# POWER.net
KiCad netlist of a schematic drawn in Altium Designer
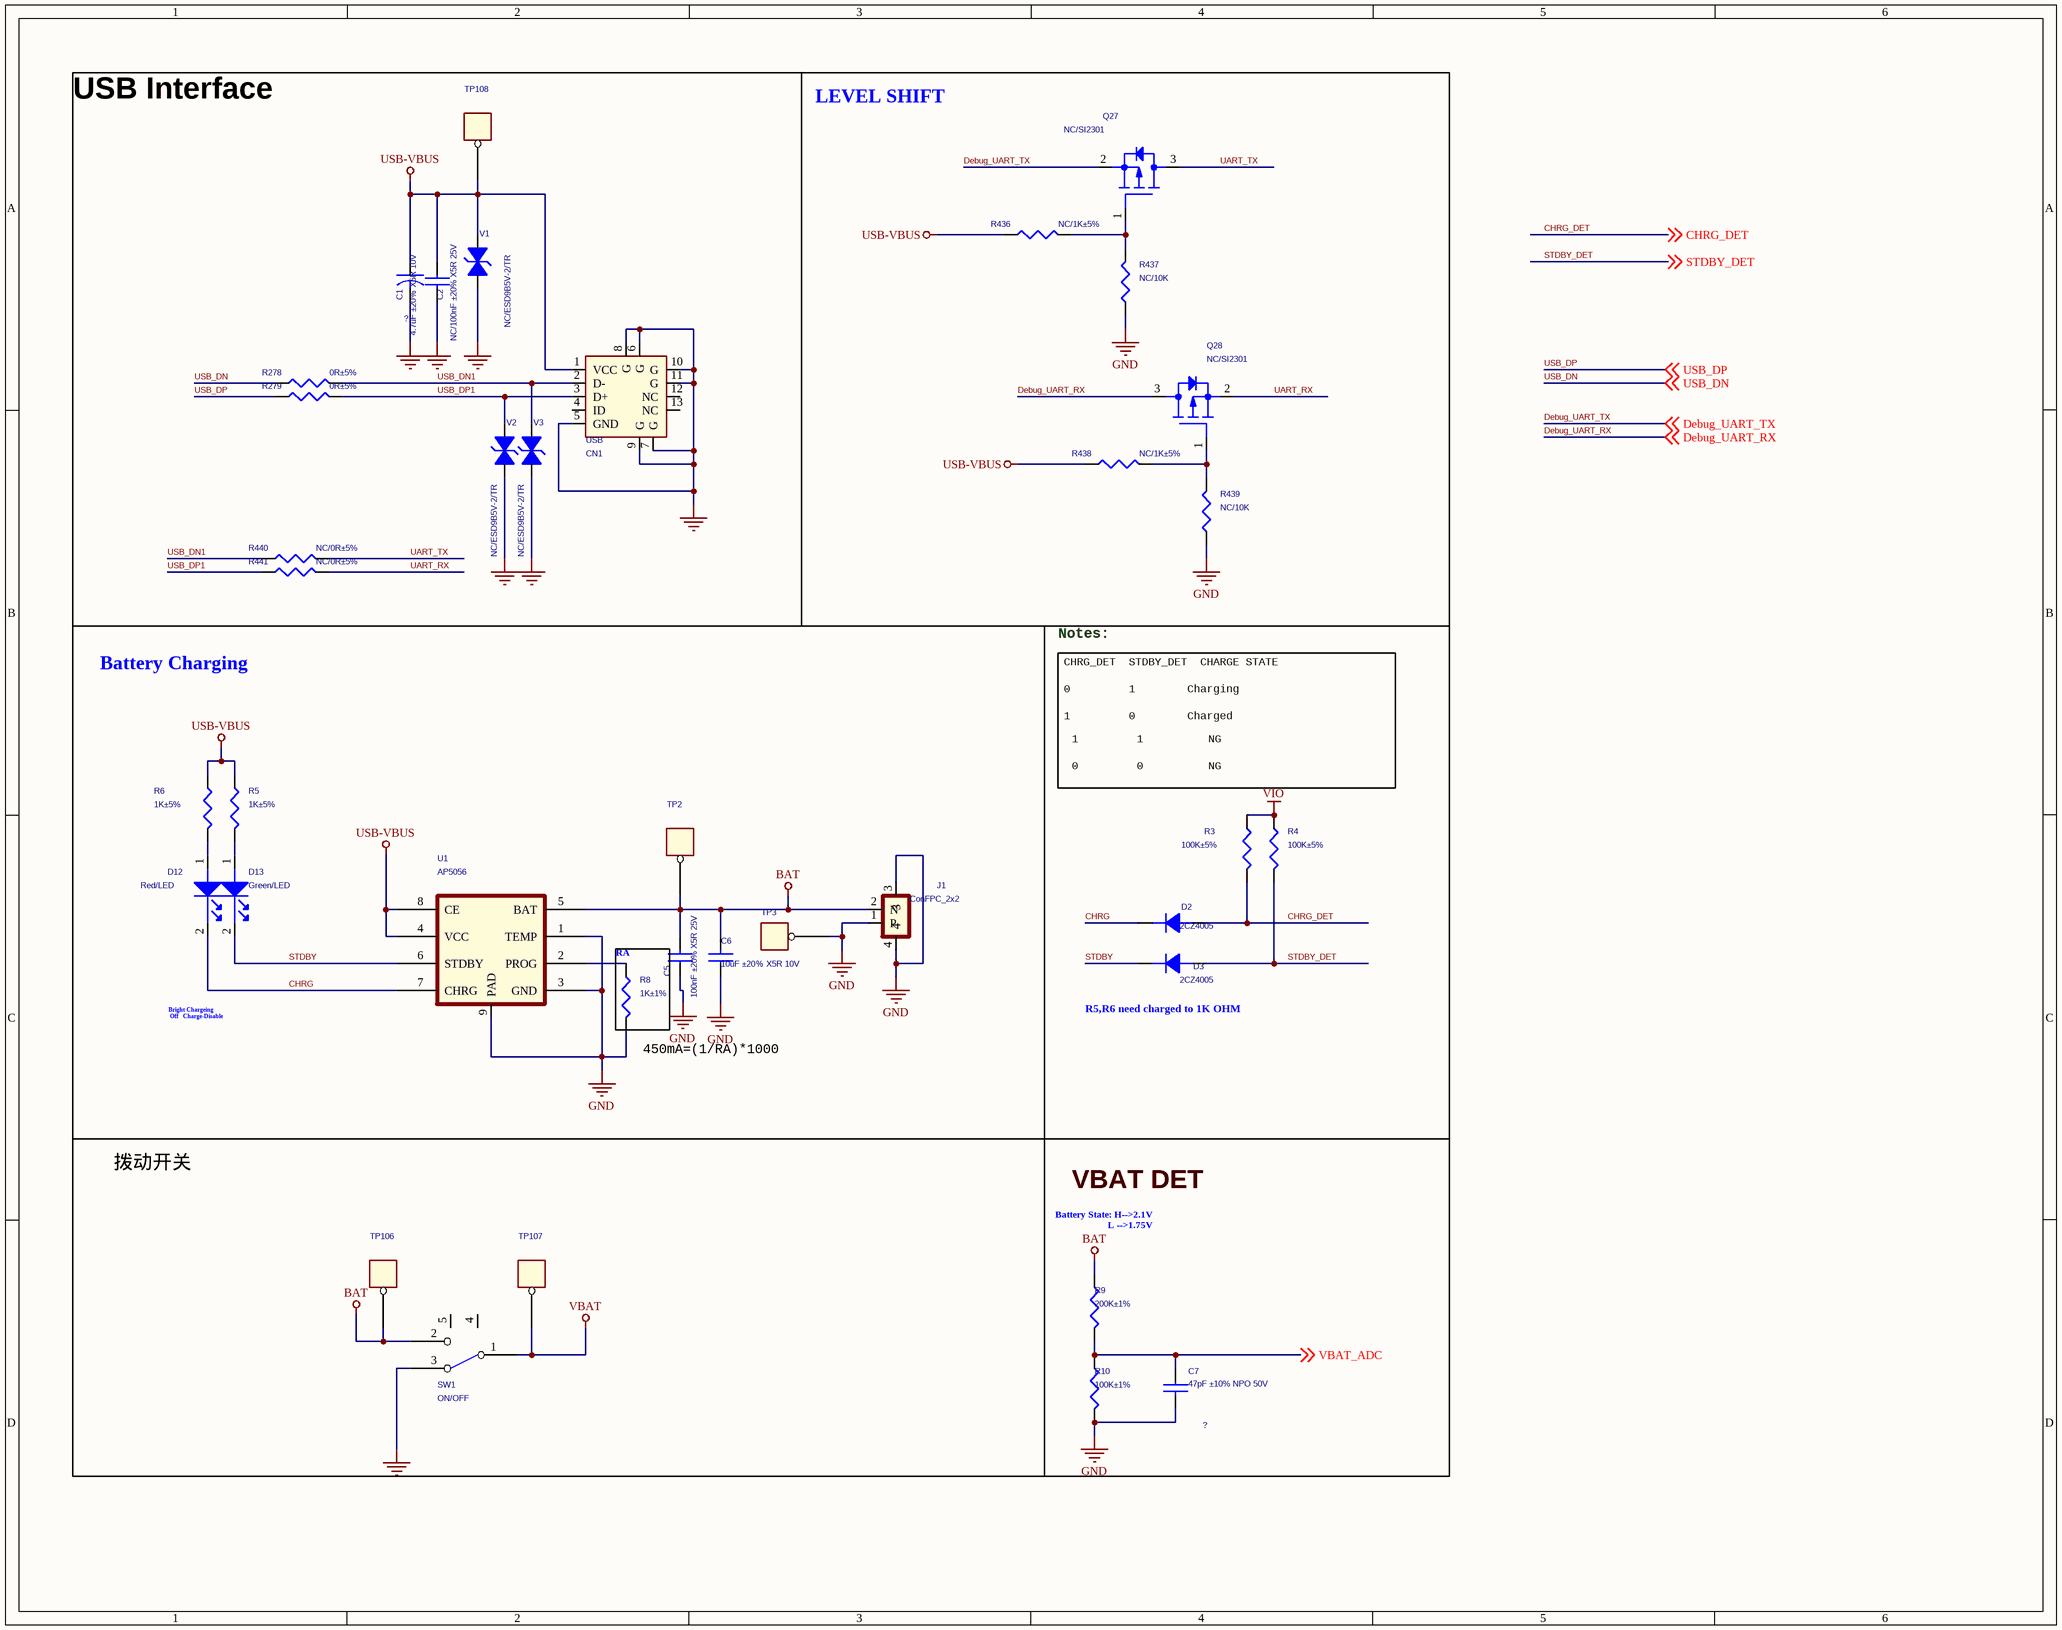
[diagram p0: POWER.SchDoc]

(export (version "E")
  (design (tool "Eeschema 10.0.6"))
  (components
    (comp (ref "C1")
      (value "4.7uF ±20％ X5R 10V")
      (footprint "C0402")
      (fields (field (name "TOLERANCE") "+/-20%") (field (name "PART_NUMBER") "105-35282-3475"))
      (libsource (lib "*") (part "CAP_Dup8"))
    )
    (comp (ref "C2")
      (value "NC/100nF ±20% X5R 25V")
      (footprint "C0402")
      (fields
        (field (name "TOLERANCE") "+/-10%")
        (field (name "VOLTAGE") "?")
        (field (name "PART_NUMBER") "105-35273-2104")
      )
      (libsource (lib "*") (part "CAP"))
    )
    (comp (ref "C5")
      (value "100nF ±20% X5R 25V")
      (footprint "C0402")
      (libsource (lib "*") (part "CAP NP_Dup6"))
    )
    (comp (ref "C6")
      (value "10uF ±20％ X5R 10V")
      (footprint "C0603")
      (libsource (lib "*") (part "CAP NP_Dup4"))
    )
    (comp (ref "C7")
      (value "47pF ±10% NPO 50V")
      (footprint "C0402")
      (fields
        (field (name "TOLERANCE") "+/-5%")
        (field (name "VOLTAGE") "?")
        (field (name "PART_NUMBER") "105-35067-2470")
      )
      (libsource (lib "*") (part "CAP_Dup9"))
    )
    (comp (ref "CN1") (value "USB") (footprint "USB_DIP5PA-GKFD") (libsource (lib "*") (part "USB TYPE A_5")))
    (comp (ref "D2") (value "2CZ4005") (footprint "SOD-123") (libsource (lib "*") (part "D_0")))
    (comp (ref "D3") (value "2CZ4005") (footprint "SOD-123") (libsource (lib "*") (part "D_0")))
    (comp (ref "D12") (value "Red/LED") (footprint "LED0603") (libsource (lib "*") (part "LED_0_Dup1")))
    (comp (ref "D13") (value "Green/LED") (footprint "LED0603") (libsource (lib "*") (part "LED_0_Dup1")))
    (comp (ref "J1") (value "ConFPC_2x2") (footprint "PL2.0-2P-SMT") (libsource (lib "*") (part "CON8_1")))
    (comp (ref "Q27")
      (value "NC/SI2301")
      (footprint "SOT-23")
      (libsource (lib "*") (part "PWRMOSFET_EP_GSD_0"))
    )
    (comp (ref "Q28")
      (value "NC/SI2301")
      (footprint "SOT-23")
      (libsource (lib "*") (part "PWRMOSFET_EP_GSD_0"))
    )
    (comp (ref "R3") (value "100K±5%") (footprint "R0402") (libsource (lib "*") (part "RESISTOR_Dup4")))
    (comp (ref "R4") (value "100K±5%") (footprint "R0402") (libsource (lib "*") (part "RESISTOR_Dup4")))
    (comp (ref "R5") (value "1K±5%") (footprint "R0402") (libsource (lib "*") (part "RESISTOR_Dup4")))
    (comp (ref "R6") (value "1K±5%") (footprint "R0402") (libsource (lib "*") (part "RESISTOR_Dup4")))
    (comp (ref "R8") (value "1K±1%") (footprint "R0402") (libsource (lib "*") (part "RESISTOR_Dup4")))
    (comp (ref "R9") (value "200K±1%") (footprint "R0402") (libsource (lib "*") (part "R_Dup5")))
    (comp (ref "R10") (value "100K±1%") (footprint "R0402") (libsource (lib "*") (part "R_Dup5")))
    (comp (ref "R278") (value "0R±5%") (footprint "R0402") (libsource (lib "*") (part "R_Dup2")))
    (comp (ref "R279") (value "0R±5%") (footprint "R0402") (libsource (lib "*") (part "R_Dup2")))
    (comp (ref "R436") (value "NC/1K±5%") (footprint "R0402") (libsource (lib "*") (part "R_Dup2")))
    (comp (ref "R437") (value "NC/10K") (footprint "R0402") (libsource (lib "*") (part "R_Dup5")))
    (comp (ref "R438") (value "NC/1K±5%") (footprint "R0402") (libsource (lib "*") (part "R_Dup2")))
    (comp (ref "R439") (value "NC/10K") (footprint "R0402") (libsource (lib "*") (part "R_Dup5")))
    (comp (ref "R440") (value "NC/0R±5%") (footprint "R0402") (libsource (lib "*") (part "R_Dup2")))
    (comp (ref "R441") (value "NC/0R±5%") (footprint "R0402") (libsource (lib "*") (part "R_Dup2")))
    (comp (ref "SW1")
      (value "ON/OFF")
      (footprint "SW_1P2D-SK12D07VG3")
      (libsource (lib "*") (part "SW KEY-SPDT_0"))
    )
    (comp (ref "TP2")
      (value "TP25RD")
      (footprint "TPC")
      (description "PAD_SM;TEST;0.025 ROUND")
      (fields (field (name "PART NUMBER") "G500-0000506"))
      (libsource (lib "*") (part "TEST_POINT"))
    )
    (comp (ref "TP3")
      (value "TP25RD")
      (footprint "TPC")
      (description "PAD_SM;TEST;0.025 ROUND")
      (fields (field (name "PART NUMBER") "G500-0000506"))
      (libsource (lib "") (part "TEST_POINT_1"))
    )
    (comp (ref "TP106")
      (value "TP25RD")
      (footprint "TPC")
      (description "PAD_SM;TEST;0.025 ROUND")
      (fields (field (name "PART NUMBER") "G500-0000506"))
      (libsource (lib "*") (part "TEST_POINT"))
    )
    (comp (ref "TP107")
      (value "TP25RD")
      (footprint "TPC")
      (description "PAD_SM;TEST;0.025 ROUND")
      (fields (field (name "PART NUMBER") "G500-0000506"))
      (libsource (lib "*") (part "TEST_POINT"))
    )
    (comp (ref "TP108")
      (value "TP25RD")
      (footprint "TPC")
      (description "PAD_SM;TEST;0.025 ROUND")
      (fields (field (name "PART NUMBER") "G500-0000506"))
      (libsource (lib "*") (part "TEST_POINT"))
    )
    (comp (ref "U1") (value "AP5056") (footprint "SOP8_PAD") (libsource (lib "*") (part "AP5057 _1")))
    (comp (ref "V1")
      (value "NC/ESD9B5V-2/TR")
      (footprint "ESD0402")
      (description "Mutilayer Varistor,,5.5V,10PF")
      (fields (field (name "MANUFACTURER") "Inpaq") (field (name "PART_NUMBER") "EB3.100NV05402A"))
      (libsource (lib "*") (part "Varistor"))
    )
    (comp (ref "V2")
      (value "NC/ESD9B5V-2/TR")
      (footprint "ESD0402")
      (description "Mutilayer Varistor,,5.5V,10PF")
      (fields (field (name "MANUFACTURER") "Inpaq") (field (name "PART_NUMBER") "EB3.100NV05402A"))
      (libsource (lib "*") (part "Varistor"))
    )
    (comp (ref "V3")
      (value "NC/ESD9B5V-2/TR")
      (footprint "ESD0402")
      (description "Mutilayer Varistor,,5.5V,10PF")
      (fields (field (name "MANUFACTURER") "Inpaq") (field (name "PART_NUMBER") "EB3.100NV05402A"))
      (libsource (lib "*") (part "Varistor"))
    )
  )
  (nets
    (net (code "1") (name "/CHRG") (class "Default")
      (node (ref "D12") (pin "2") (pinfunction "CATHODE_2") (pintype "passive"))
      (node (ref "D2") (pin "2") (pinfunction "2_2") (pintype "passive"))
      (node (ref "U1") (pin "7") (pinfunction "CHRG_7") (pintype "passive"))
    )
    (net (code "2") (name "/STDBY") (class "Default")
      (node (ref "D13") (pin "2") (pinfunction "CATHODE_2") (pintype "passive"))
      (node (ref "D3") (pin "2") (pinfunction "2_2") (pintype "passive"))
      (node (ref "U1") (pin "6") (pinfunction "STDBY_6") (pintype "passive"))
    )
    (net (code "3") (name "/UART_RX") (class "Default")
      (node (ref "Q28") (pin "2") (pinfunction "SOURCE_2") (pintype "passive"))
      (node (ref "R441") (pin "2") (pinfunction "2_2") (pintype "passive"))
    )
    (net (code "4") (name "/UART_TX") (class "Default")
      (node (ref "Q27") (pin "3") (pinfunction "DRAIN_3") (pintype "passive"))
      (node (ref "R440") (pin "2") (pinfunction "2_2") (pintype "passive"))
    )
    (net (code "5") (name "/USB_DN1") (class "Default")
      (node (ref "CN1") (pin "2") (pinfunction "D-_2") (pintype "passive"))
      (node (ref "R278") (pin "2") (pinfunction "2_2") (pintype "passive"))
      (node (ref "R440") (pin "1") (pinfunction "1_1") (pintype "passive"))
      (node (ref "V3") (pin "1") (pinfunction "I/O1_1") (pintype "passive"))
    )
    (net (code "6") (name "/USB_DP1") (class "Default")
      (node (ref "CN1") (pin "3") (pinfunction "D+_3") (pintype "passive"))
      (node (ref "R279") (pin "2") (pinfunction "2_2") (pintype "passive"))
      (node (ref "R441") (pin "1") (pinfunction "1_1") (pintype "passive"))
      (node (ref "V2") (pin "1") (pinfunction "I/O1_1") (pintype "passive"))
    )
    (net (code "7") (name "BAT") (class "Default")
      (node (ref "C5") (pin "2") (pinfunction "2_2") (pintype "passive"))
      (node (ref "C6") (pin "2") (pinfunction "2_2") (pintype "passive"))
      (node (ref "J1") (pin "2") (pinfunction "N_2") (pintype "passive"))
      (node (ref "R9") (pin "1") (pinfunction "1_1") (pintype "passive"))
      (node (ref "SW1") (pin "2") (pinfunction "NO_2") (pintype "passive"))
      (node (ref "TP106") (pin "1") (pinfunction "TP1_1") (pintype "passive"))
      (node (ref "TP2") (pin "1") (pinfunction "TP1_1") (pintype "passive"))
      (node (ref "U1") (pin "5") (pinfunction "BAT_5") (pintype "passive"))
    )
    (net (code "8") (name "CHRG_DET") (class "Default")
      (node (ref "D2") (pin "1") (pinfunction "1_1") (pintype "passive"))
      (node (ref "R3") (pin "2") (pinfunction "2_2") (pintype "passive"))
    )
    (net (code "9") (name "Debug_UART_RX") (class "Default")
      (node (ref "Q28") (pin "3") (pinfunction "DRAIN_3") (pintype "passive"))
    )
    (net (code "10") (name "Debug_UART_TX") (class "Default")
      (node (ref "Q27") (pin "2") (pinfunction "SOURCE_2") (pintype "passive"))
    )
    (net (code "11") (name "GND") (class "Default")
      (node (ref "C1") (pin "2") (pinfunction "2_2") (pintype "passive"))
      (node (ref "C2") (pin "2") (pinfunction "Pin2_2") (pintype "passive"))
      (node (ref "C5") (pin "1") (pinfunction "1_1") (pintype "passive"))
      (node (ref "C6") (pin "1") (pinfunction "1_1") (pintype "passive"))
      (node (ref "C7") (pin "2") (pinfunction "Pin2_2") (pintype "passive"))
      (node (ref "CN1") (pin "10") (pinfunction "G_10") (pintype "passive"))
      (node (ref "CN1") (pin "11") (pinfunction "G_11") (pintype "passive"))
      (node (ref "CN1") (pin "5") (pinfunction "GND_5") (pintype "passive"))
      (node (ref "CN1") (pin "6") (pinfunction "G_6") (pintype "passive"))
      (node (ref "CN1") (pin "7") (pinfunction "G_7") (pintype "passive"))
      (node (ref "CN1") (pin "8") (pinfunction "G_8") (pintype "passive"))
      (node (ref "CN1") (pin "9") (pinfunction "G_9") (pintype "passive"))
      (node (ref "J1") (pin "1") (pinfunction "P_1") (pintype "passive"))
      (node (ref "J1") (pin "3") (pinfunction "3_3") (pintype "passive"))
      (node (ref "J1") (pin "4") (pinfunction "4_4") (pintype "passive"))
      (node (ref "R10") (pin "2") (pinfunction "2_2") (pintype "passive"))
      (node (ref "R437") (pin "1") (pinfunction "1_1") (pintype "passive"))
      (node (ref "R439") (pin "1") (pinfunction "1_1") (pintype "passive"))
      (node (ref "R8") (pin "1") (pinfunction "1_1") (pintype "passive"))
      (node (ref "SW1") (pin "3") (pinfunction "NC_3") (pintype "passive"))
      (node (ref "TP3") (pin "1") (pinfunction "TP1_1") (pintype "passive"))
      (node (ref "U1") (pin "1") (pinfunction "TEMP_1") (pintype "passive"))
      (node (ref "U1") (pin "3") (pinfunction "GND_3") (pintype "passive"))
      (node (ref "U1") (pin "9") (pinfunction "PAD_9") (pintype "passive"))
      (node (ref "V1") (pin "2") (pinfunction "I/O2_2") (pintype "passive"))
      (node (ref "V2") (pin "2") (pinfunction "I/O2_2") (pintype "passive"))
      (node (ref "V3") (pin "2") (pinfunction "I/O2_2") (pintype "passive"))
    )
    (net (code "12") (name "Net-(D12-ANODE)") (class "Default")
      (node (ref "D12") (pin "1") (pinfunction "ANODE_1") (pintype "passive"))
      (node (ref "R6") (pin "1") (pinfunction "1_1") (pintype "passive"))
    )
    (net (code "13") (name "Net-(D13-ANODE)") (class "Default")
      (node (ref "D13") (pin "1") (pinfunction "ANODE_1") (pintype "passive"))
      (node (ref "R5") (pin "1") (pinfunction "1_1") (pintype "passive"))
    )
    (net (code "14") (name "Net-(Q27-GATE)") (class "Default")
      (node (ref "Q27") (pin "1") (pinfunction "GATE_1") (pintype "passive"))
      (node (ref "R436") (pin "2") (pinfunction "2_2") (pintype "passive"))
      (node (ref "R437") (pin "2") (pinfunction "2_2") (pintype "passive"))
    )
    (net (code "15") (name "Net-(Q28-GATE)") (class "Default")
      (node (ref "Q28") (pin "1") (pinfunction "GATE_1") (pintype "passive"))
      (node (ref "R438") (pin "2") (pinfunction "2_2") (pintype "passive"))
      (node (ref "R439") (pin "2") (pinfunction "2_2") (pintype "passive"))
    )
    (net (code "16") (name "Net-(U1-PROG)") (class "Default")
      (node (ref "R8") (pin "2") (pinfunction "2_2") (pintype "passive"))
      (node (ref "U1") (pin "2") (pinfunction "PROG_2") (pintype "passive"))
    )
    (net (code "17") (name "STDBY_DET") (class "Default")
      (node (ref "D3") (pin "1") (pinfunction "1_1") (pintype "passive"))
      (node (ref "R4") (pin "2") (pinfunction "2_2") (pintype "passive"))
    )
    (net (code "18") (name "USB-VBUS") (class "Default")
      (node (ref "C1") (pin "1") (pinfunction "1_1") (pintype "passive"))
      (node (ref "C2") (pin "1") (pinfunction "Pin1_1") (pintype "passive"))
      (node (ref "CN1") (pin "1") (pinfunction "VCC_1") (pintype "passive"))
      (node (ref "R436") (pin "1") (pinfunction "1_1") (pintype "passive"))
      (node (ref "R438") (pin "1") (pinfunction "1_1") (pintype "passive"))
      (node (ref "R5") (pin "2") (pinfunction "2_2") (pintype "passive"))
      (node (ref "R6") (pin "2") (pinfunction "2_2") (pintype "passive"))
      (node (ref "TP108") (pin "1") (pinfunction "TP1_1") (pintype "passive"))
      (node (ref "U1") (pin "4") (pinfunction "VCC_4") (pintype "passive"))
      (node (ref "U1") (pin "8") (pinfunction "CE_8") (pintype "passive"))
      (node (ref "V1") (pin "1") (pinfunction "I/O1_1") (pintype "passive"))
    )
    (net (code "19") (name "USB_DN") (class "Default")
      (node (ref "R278") (pin "1") (pinfunction "1_1") (pintype "passive"))
    )
    (net (code "20") (name "USB_DP") (class "Default")
      (node (ref "R279") (pin "1") (pinfunction "1_1") (pintype "passive"))
    )
    (net (code "21") (name "VBAT") (class "Default")
      (node (ref "SW1") (pin "1") (pinfunction "COMMON_1") (pintype "passive"))
      (node (ref "TP107") (pin "1") (pinfunction "TP1_1") (pintype "passive"))
    )
    (net (code "22") (name "VBAT_ADC") (class "Default")
      (node (ref "C7") (pin "1") (pinfunction "Pin1_1") (pintype "passive"))
      (node (ref "R10") (pin "1") (pinfunction "1_1") (pintype "passive"))
      (node (ref "R9") (pin "2") (pinfunction "2_2") (pintype "passive"))
    )
    (net (code "23") (name "VIO") (class "Default")
      (node (ref "R3") (pin "1") (pinfunction "1_1") (pintype "passive"))
      (node (ref "R4") (pin "1") (pinfunction "1_1") (pintype "passive"))
    )
    (net (code "24") (name "unconnected-(CN1-ID-Pad4)") (class "Default")
      (node (ref "CN1") (pin "4") (pinfunction "ID_4") (pintype "passive"))
    )
    (net (code "25") (name "unconnected-(CN1-NC-Pad12)") (class "Default")
      (node (ref "CN1") (pin "12") (pinfunction "NC_12") (pintype "passive"))
    )
    (net (code "26") (name "unconnected-(CN1-NC-Pad13)") (class "Default")
      (node (ref "CN1") (pin "13") (pinfunction "NC_13") (pintype "passive"))
    )
    (net (code "27") (name "unconnected-(SW1-NC-Pad4)") (class "Default")
      (node (ref "SW1") (pin "4") (pinfunction "NC_4") (pintype "passive"))
    )
    (net (code "28") (name "unconnected-(SW1-NC-Pad5)") (class "Default")
      (node (ref "SW1") (pin "5") (pinfunction "NC_5") (pintype "passive"))
    )
  )
)
